# board.net
KiCad netlist of a schematic drawn in EAGLE
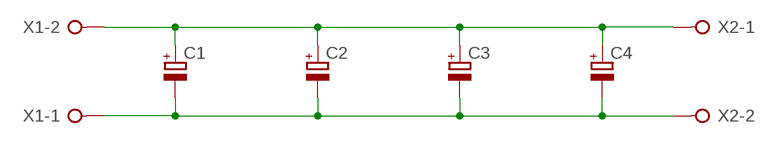
[diagram p0: schematic, sheet 1]

(export (version "E")
  (design (tool "Eeschema 10.0.6"))
  (components
    (comp (ref "C1")
      (value "CPOL-EUE10-35")
      (footprint "eagle-import:EB35D")
      (libsource (lib "eagle-import") (part "CPOL-EUE10-35"))
    )
    (comp (ref "C2")
      (value "CPOL-EUE10-35")
      (footprint "eagle-import:EB35D")
      (libsource (lib "eagle-import") (part "CPOL-EUE10-35"))
    )
    (comp (ref "C3")
      (value "CPOL-EUE10-35")
      (footprint "eagle-import:EB35D")
      (libsource (lib "eagle-import") (part "CPOL-EUE10-35"))
    )
    (comp (ref "C4")
      (value "CPOL-EUE10-35")
      (footprint "eagle-import:EB35D")
      (libsource (lib "eagle-import") (part "CPOL-EUE10-35"))
    )
    (comp (ref "X1")
      (value "W237-02P")
      (footprint "eagle-import:W237-132")
      (libsource (lib "eagle-import") (part "W237-02P"))
    )
    (comp (ref "X2")
      (value "W237-02P")
      (footprint "eagle-import:W237-132")
      (libsource (lib "eagle-import") (part "W237-02P"))
    )
  )
  (nets
    (net (code "1") (name "Net-(X1A-KL)") (class "Default")
      (node (ref "C1") (pin "-") (pinfunction "-_-") (pintype "passive"))
      (node (ref "C2") (pin "-") (pinfunction "-_-") (pintype "passive"))
      (node (ref "C3") (pin "-") (pinfunction "-_-") (pintype "passive"))
      (node (ref "C4") (pin "-") (pinfunction "-_-") (pintype "passive"))
      (node (ref "X1") (pin "1") (pinfunction "KL_1") (pintype "passive"))
      (node (ref "X2") (pin "2") (pinfunction "KL_2") (pintype "passive"))
    )
    (net (code "2") (name "Net-(X1B-KL)") (class "Default")
      (node (ref "C1") (pin "+") (pinfunction "+_+") (pintype "passive"))
      (node (ref "C2") (pin "+") (pinfunction "+_+") (pintype "passive"))
      (node (ref "C3") (pin "+") (pinfunction "+_+") (pintype "passive"))
      (node (ref "C4") (pin "+") (pinfunction "+_+") (pintype "passive"))
      (node (ref "X1") (pin "2") (pinfunction "KL_2") (pintype "passive"))
      (node (ref "X2") (pin "1") (pinfunction "KL_1") (pintype "passive"))
    )
  )
)
